# tomada_esp-tom.net
KiCad netlist of a schematic drawn in EAGLE
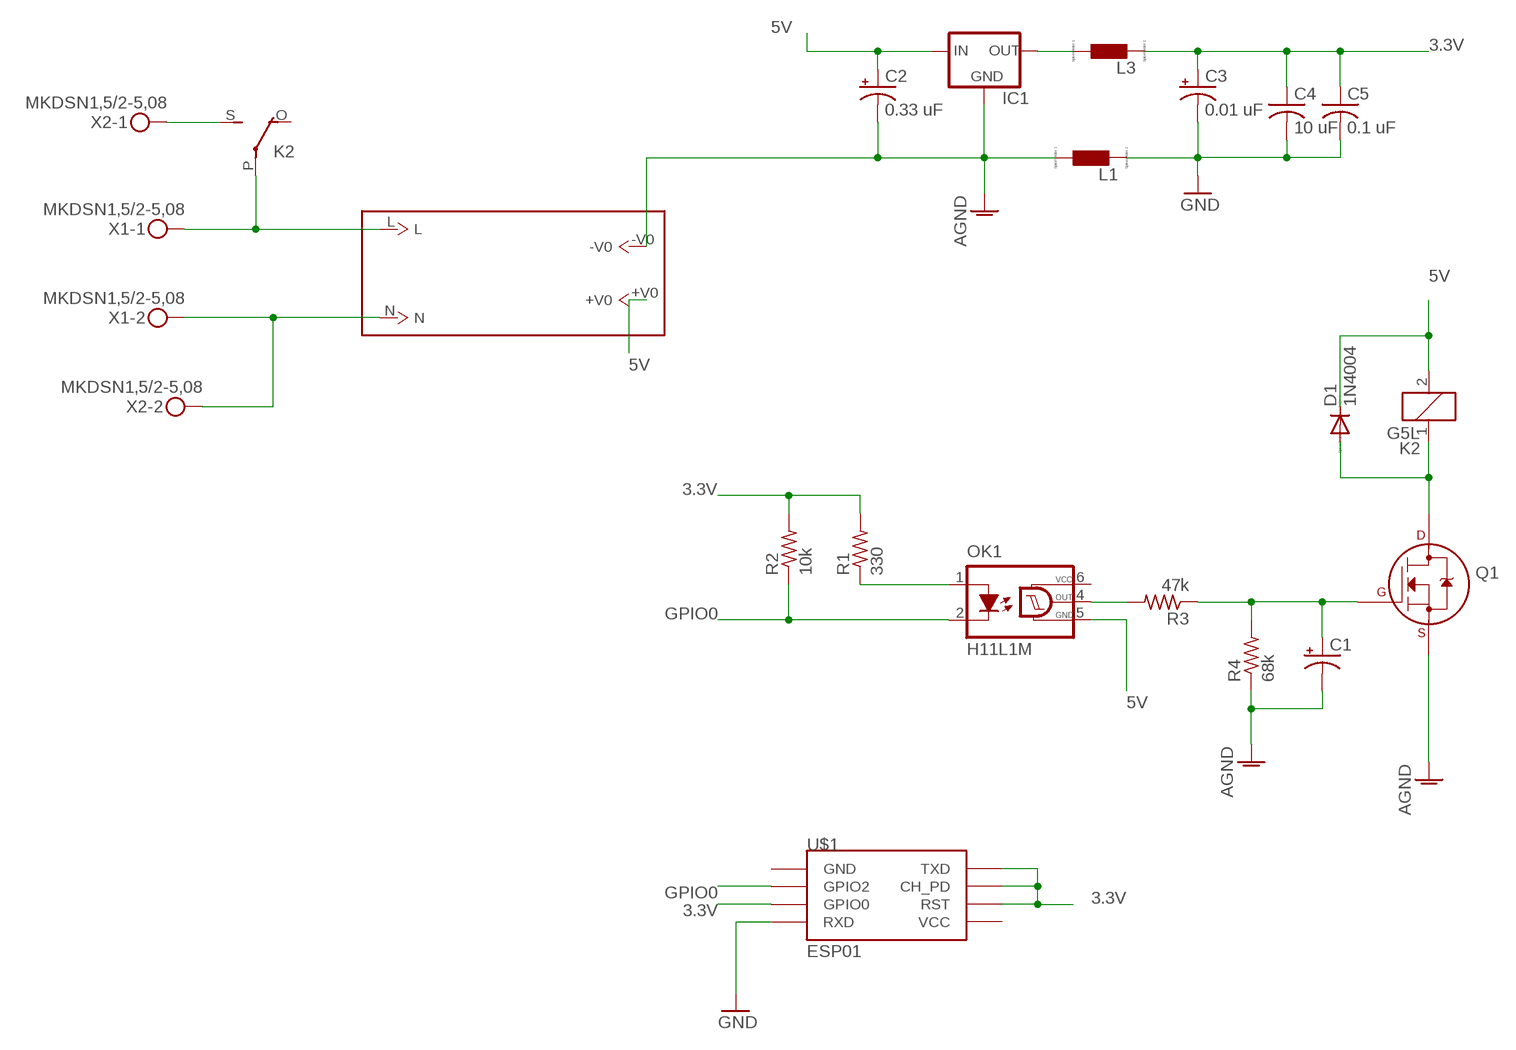
[diagram p0: schematic, sheet 1]

(export (version "E")
  (design (tool "Eeschema 10.0.6"))
  (components
    (comp (ref "C1")
      (value "CPOL-USE2-5")
      (footprint "eagle-import:E2-5")
      (libsource (lib "eagle-import") (part "CPOL-USE2-5"))
    )
    (comp (ref "C2")
      (value "0.33 uF")
      (footprint "eagle-import:E2-5")
      (libsource (lib "eagle-import") (part "CPOL-USE2-5"))
    )
    (comp (ref "C3")
      (value "0.01 uF")
      (footprint "eagle-import:E2-5")
      (libsource (lib "eagle-import") (part "CPOL-USE2-5"))
    )
    (comp (ref "C4")
      (value "10 uF")
      (footprint "eagle-import:C025-024X044")
      (libsource (lib "eagle-import") (part "C-US025-024X044"))
    )
    (comp (ref "C5")
      (value "0.1 uF")
      (footprint "eagle-import:C025-024X044")
      (libsource (lib "eagle-import") (part "C-US025-024X044"))
    )
    (comp (ref "D1")
      (value "1N4004")
      (footprint "eagle-import:DO41-10")
      (libsource (lib "eagle-import") (part "1N4004"))
    )
    (comp (ref "IC1")
      (value "78LXX")
      (footprint "eagle-import:78LXX")
      (libsource (lib "eagle-import") (part "78LXX"))
    )
    (comp (ref "K2")
      (value "G5L")
      (footprint "eagle-import:G5LE")
      (libsource (lib "eagle-import") (part "G5L"))
    )
    (comp (ref "L1")
      (value "L0207/10")
      (footprint "eagle-import:0207_10")
      (libsource (lib "eagle-import") (part "L0207/10"))
    )
    (comp (ref "L3")
      (value "L0207/10")
      (footprint "eagle-import:0207_10")
      (libsource (lib "eagle-import") (part "L0207/10"))
    )
    (comp (ref "OK1")
      (value "H11L1M")
      (footprint "eagle-import:DIL06")
      (fields (field (name "MF") "FAIRCHILD SEMICONDUCTOR") (field (name "MPN") "H11L1-M"))
      (libsource (lib "eagle-import") (part "H11LM1"))
    )
    (comp (ref "Q1")
      (value "2N7000_TO92")
      (footprint "eagle-import:TO-92")
      (libsource (lib "eagle-import") (part "2N700_TO920"))
    )
    (comp (ref "R1")
      (value "330")
      (footprint "eagle-import:0204_7")
      (libsource (lib "eagle-import") (part "R-US_0204/7"))
    )
    (comp (ref "R2")
      (value "10k")
      (footprint "eagle-import:0204_7")
      (libsource (lib "eagle-import") (part "R-US_0204/7"))
    )
    (comp (ref "R3")
      (value "47k")
      (footprint "eagle-import:0204_7")
      (libsource (lib "eagle-import") (part "R-US_0204/7"))
    )
    (comp (ref "R4")
      (value "68k")
      (footprint "eagle-import:0204_7")
      (libsource (lib "eagle-import") (part "R-US_0204/7"))
    )
    (comp (ref "U$1")
      (value "ESP01")
      (footprint "eagle-import:ESP01")
      (libsource (lib "eagle-import") (part "ESP01"))
    )
    (comp (ref "U$2")
      (value "NA03-T2S05")
      (footprint "eagle-import:NA03-T2S05")
      (libsource (lib "eagle-import") (part "NA03-T2S05"))
    )
    (comp (ref "X1")
      (value "MKDSN1,5/2-5,08")
      (footprint "eagle-import:MKDSN1,5_2-5,08")
      (libsource (lib "eagle-import") (part "MKDSN1,5/2-5,08"))
    )
    (comp (ref "X2")
      (value "MKDSN1,5/2-5,08")
      (footprint "eagle-import:MKDSN1,5_2-5,08")
      (libsource (lib "eagle-import") (part "MKDSN1,5/2-5,08"))
    )
  )
  (nets
    (net (code "1") (name "/3.3V") (class "Default")
      (node (ref "C3") (pin "+") (pinfunction "+_+") (pintype "passive"))
      (node (ref "C4") (pin "1") (pinfunction "1_1") (pintype "passive"))
      (node (ref "C5") (pin "1") (pinfunction "1_1") (pintype "passive"))
      (node (ref "L3") (pin "2") (pinfunction "2_2") (pintype "passive"))
      (node (ref "R1") (pin "2") (pinfunction "2_2") (pintype "passive"))
      (node (ref "R2") (pin "2") (pinfunction "2_2") (pintype "passive"))
      (node (ref "U$1") (pin "CH_PD") (pinfunction "CH_PD_CH_PD") (pintype "bidirectional"))
      (node (ref "U$1") (pin "GPIO0") (pinfunction "GPIO0_GPIO0") (pintype "bidirectional"))
      (node (ref "U$1") (pin "RST") (pinfunction "RST_RST") (pintype "bidirectional"))
      (node (ref "U$1") (pin "TX") (pinfunction "TXD_TX") (pintype "bidirectional"))
    )
    (net (code "2") (name "/5V") (class "Default")
      (node (ref "C2") (pin "+") (pinfunction "+_+") (pintype "passive"))
      (node (ref "D1") (pin "C") (pinfunction "C_C") (pintype "passive"))
      (node (ref "IC1") (pin "IN") (pinfunction "IN_IN") (pintype "input"))
      (node (ref "K2") (pin "2") (pinfunction "2_2") (pintype "passive"))
      (node (ref "OK1") (pin "5") (pinfunction "GND_5") (pintype "power_in"))
      (node (ref "U$2") (pin "+V0") (pinfunction "+V0_+V0") (pintype "bidirectional"))
    )
    (net (code "3") (name "/GPIO0") (class "Default")
      (node (ref "OK1") (pin "2") (pinfunction "C_2") (pintype "passive"))
      (node (ref "R2") (pin "1") (pinfunction "1_1") (pintype "passive"))
      (node (ref "U$1") (pin "GPIO2") (pinfunction "GPIO2_GPIO2") (pintype "bidirectional"))
    )
    (net (code "4") (name "/VCC") (class "Default")
      (node (ref "OK1") (pin "6") (pinfunction "VCC_6") (pintype "power_in"))
    )
    (net (code "5") (name "AGND") (class "Default")
      (node (ref "C1") (pin "-") (pinfunction "-_-") (pintype "passive"))
      (node (ref "C2") (pin "-") (pinfunction "-_-") (pintype "passive"))
      (node (ref "IC1") (pin "GND") (pinfunction "GND_GND") (pintype "input"))
      (node (ref "L1") (pin "1") (pinfunction "1_1") (pintype "passive"))
      (node (ref "Q1") (pin "1") (pinfunction "S_1") (pintype "bidirectional"))
      (node (ref "R4") (pin "1") (pinfunction "1_1") (pintype "passive"))
      (node (ref "U$2") (pin "-V0") (pinfunction "-V0_-V0") (pintype "bidirectional"))
    )
    (net (code "6") (name "GND") (class "Default")
      (node (ref "C3") (pin "-") (pinfunction "-_-") (pintype "passive"))
      (node (ref "C4") (pin "2") (pinfunction "2_2") (pintype "passive"))
      (node (ref "C5") (pin "2") (pinfunction "2_2") (pintype "passive"))
      (node (ref "L1") (pin "2") (pinfunction "2_2") (pintype "passive"))
      (node (ref "U$1") (pin "RX") (pinfunction "RXD_RX") (pintype "bidirectional"))
    )
    (net (code "7") (name "Net-(IC1-PadOUT)") (class "Default")
      (node (ref "IC1") (pin "OUT") (pinfunction "OUT_OUT") (pintype "passive"))
      (node (ref "L3") (pin "1") (pinfunction "1_1") (pintype "passive"))
    )
    (net (code "8") (name "Net-(OK1-A)") (class "Default")
      (node (ref "OK1") (pin "1") (pinfunction "A_1") (pintype "passive"))
      (node (ref "R1") (pin "1") (pinfunction "1_1") (pintype "passive"))
    )
    (net (code "9") (name "Net-(OK1-OUT)") (class "Default")
      (node (ref "OK1") (pin "4") (pinfunction "OUT_4") (pintype "output"))
      (node (ref "R3") (pin "2") (pinfunction "2_2") (pintype "passive"))
    )
    (net (code "10") (name "Net-(Q1-D)") (class "Default")
      (node (ref "D1") (pin "A") (pinfunction "A_A") (pintype "passive"))
      (node (ref "K2") (pin "1") (pinfunction "1_1") (pintype "passive"))
      (node (ref "Q1") (pin "3") (pinfunction "D_3") (pintype "bidirectional"))
    )
    (net (code "11") (name "Net-(Q1-G)") (class "Default")
      (node (ref "C1") (pin "+") (pinfunction "+_+") (pintype "passive"))
      (node (ref "Q1") (pin "2") (pinfunction "G_2") (pintype "tri_state"))
      (node (ref "R3") (pin "1") (pinfunction "1_1") (pintype "passive"))
      (node (ref "R4") (pin "2") (pinfunction "2_2") (pintype "passive"))
    )
    (net (code "12") (name "Net-(X1A-KL)") (class "Default")
      (node (ref "K2") (pin "P") (pinfunction "P_P") (pintype "passive"))
      (node (ref "U$2") (pin "L") (pinfunction "L_L") (pintype "bidirectional"))
      (node (ref "X1") (pin "1") (pinfunction "KL_1") (pintype "passive"))
    )
    (net (code "13") (name "Net-(X1B-KL)") (class "Default")
      (node (ref "U$2") (pin "N") (pinfunction "N_N") (pintype "bidirectional"))
      (node (ref "X1") (pin "2") (pinfunction "KL_2") (pintype "passive"))
      (node (ref "X2") (pin "2") (pinfunction "KL_2") (pintype "passive"))
    )
    (net (code "14") (name "Net-(X2A-KL)") (class "Default")
      (node (ref "K2") (pin "S") (pinfunction "S_S") (pintype "passive"))
      (node (ref "X2") (pin "1") (pinfunction "KL_1") (pintype "passive"))
    )
    (net (code "15") (name "unconnected-(K2-PadO)") (class "Default")
      (node (ref "K2") (pin "O") (pinfunction "O_O") (pintype "passive"))
    )
    (net (code "16") (name "unconnected-(U$1-PadGND)") (class "Default")
      (node (ref "U$1") (pin "GND") (pinfunction "GND_GND") (pintype "bidirectional"))
    )
    (net (code "17") (name "unconnected-(U$1-PadVCC)") (class "Default")
      (node (ref "U$1") (pin "VCC") (pinfunction "VCC_VCC") (pintype "bidirectional"))
    )
  )
)
